# POWER_MUX.net
KiCad netlist of a schematic drawn in Altium Designer
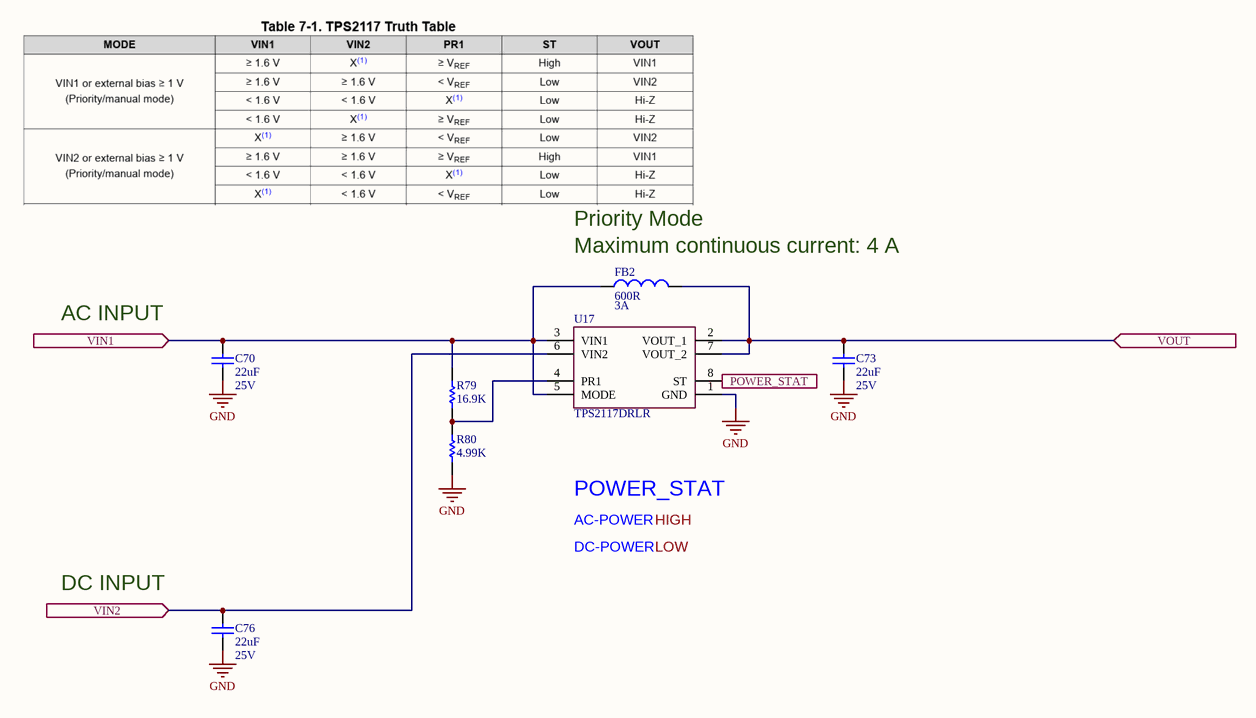
[diagram p0: POWER_MUX.SchDoc]

(export (version "E")
  (design (tool "Eeschema 10.0.6"))
  (components
    (comp (ref "C70")
      (value "22uF")
      (footprint "CAP_0805")
      (description "CAP CER 22UF 25V X5R 0805")
      (fields
        (field (name "VOLTAGE") "25V")
        (field (name "MANUFACTURER") "Samsung")
        (field (name "MANUFACTURER PART NUMBER") "CL21A226MAYNNNE")
      )
      (libsource (lib "open-components") (part "CAP"))
    )
    (comp (ref "C73")
      (value "22uF")
      (footprint "CAP_0805")
      (description "CAP CER 22UF 25V X5R 0805")
      (fields
        (field (name "VOLTAGE") "25V")
        (field (name "MANUFACTURER") "Samsung")
        (field (name "MANUFACTURER PART NUMBER") "CL21A226MAYNNNE")
      )
      (libsource (lib "open-components") (part "CAP"))
    )
    (comp (ref "C76")
      (value "22uF")
      (footprint "CAP_0805")
      (description "CAP CER 22UF 25V X5R 0805")
      (fields
        (field (name "VOLTAGE") "25V")
        (field (name "MANUFACTURER") "Samsung")
        (field (name "MANUFACTURER PART NUMBER") "CL21A226MAYNNNE")
      )
      (libsource (lib "open-components") (part "CAP"))
    )
    (comp (ref "FB2")
      (value "600R")
      (footprint "BEADC3225X280N")
      (description "FERRITE BEAD 1210 600R 3A SMD")
      (fields
        (field (name "MANUFACTURER") "Taiyo Yuden")
        (field (name "MANUFACTURER PART NUMBER") "FBMH3225HM601NT")
        (field (name "CURRENT") "3A")
      )
      (libsource (lib "open-components") (part "IND"))
    )
    (comp (ref "R79")
      (value "16.9K")
      (footprint "RES_0603")
      (description "RES.(1608) 0603 16.9K Ohms 1% 1/10W-S 100PPM")
      (fields
        (field (name "MANUFACTURER") "ROYALOHM")
        (field (name "MANUFACTURER PART NUMBER") "0603SAF1692T5E")
      )
      (libsource (lib "open-components") (part "RES"))
    )
    (comp (ref "R80")
      (value "4.99K")
      (footprint "RES_0603")
      (description "RES.(1608) 0603 4.99K Ohms 1% 1/10W-S 100PPM")
      (fields
        (field (name "MANUFACTURER") "ROYALOHM")
        (field (name "MANUFACTURER PART NUMBER") "0603SAF4991T5E")
      )
      (libsource (lib "open-components") (part "RES"))
    )
    (comp (ref "U17")
      (value "TPS2117DRLR")
      (footprint "SamacSys:SOTFL50P160X60-8N")
      (description "1.6-V TO 5.5-V, 20-M, 4-A LOW IQ")
      (fields (field (name "MANUFACTURER") "Texas Instruments"))
      (libsource (lib "MTOSOS_R02") (part "TPS2117DRLR"))
    )
  )
  (nets
    (net (code "1") (name "/POWER_STAT") (class "Default")
      (node (ref "U17") (pin "8") (pinfunction "ST_8") (pintype "passive"))
    )
    (net (code "2") (name "/VIN1") (class "Default")
      (node (ref "C70") (pin "1") (pinfunction "1_1") (pintype "passive"))
      (node (ref "FB2") (pin "1") (pinfunction "1_1") (pintype "passive"))
      (node (ref "R79") (pin "2") (pinfunction "2_2") (pintype "passive"))
      (node (ref "U17") (pin "3") (pinfunction "VIN1_3") (pintype "passive"))
      (node (ref "U17") (pin "5") (pinfunction "MODE_5") (pintype "passive"))
    )
    (net (code "3") (name "/VIN2") (class "Default")
      (node (ref "C76") (pin "1") (pinfunction "1_1") (pintype "passive"))
      (node (ref "U17") (pin "6") (pinfunction "VIN2_6") (pintype "passive"))
    )
    (net (code "4") (name "/VOUT") (class "Default")
      (node (ref "C73") (pin "1") (pinfunction "1_1") (pintype "passive"))
      (node (ref "FB2") (pin "2") (pinfunction "2_2") (pintype "passive"))
      (node (ref "U17") (pin "2") (pinfunction "VOUT_1_2") (pintype "passive"))
      (node (ref "U17") (pin "7") (pinfunction "VOUT_2_7") (pintype "passive"))
    )
    (net (code "5") (name "GND") (class "Default")
      (node (ref "C70") (pin "2") (pinfunction "2_2") (pintype "passive"))
      (node (ref "C73") (pin "2") (pinfunction "2_2") (pintype "passive"))
      (node (ref "C76") (pin "2") (pinfunction "2_2") (pintype "passive"))
      (node (ref "R80") (pin "1") (pinfunction "1_1") (pintype "passive"))
      (node (ref "U17") (pin "1") (pinfunction "GND_1") (pintype "passive"))
    )
    (net (code "6") (name "Net-(U17-PR1)") (class "Default")
      (node (ref "R79") (pin "1") (pinfunction "1_1") (pintype "passive"))
      (node (ref "R80") (pin "2") (pinfunction "2_2") (pintype "passive"))
      (node (ref "U17") (pin "4") (pinfunction "PR1_4") (pintype "passive"))
    )
  )
)
